# usbport-power-controller.net
KiCad netlist of a schematic drawn in EAGLE
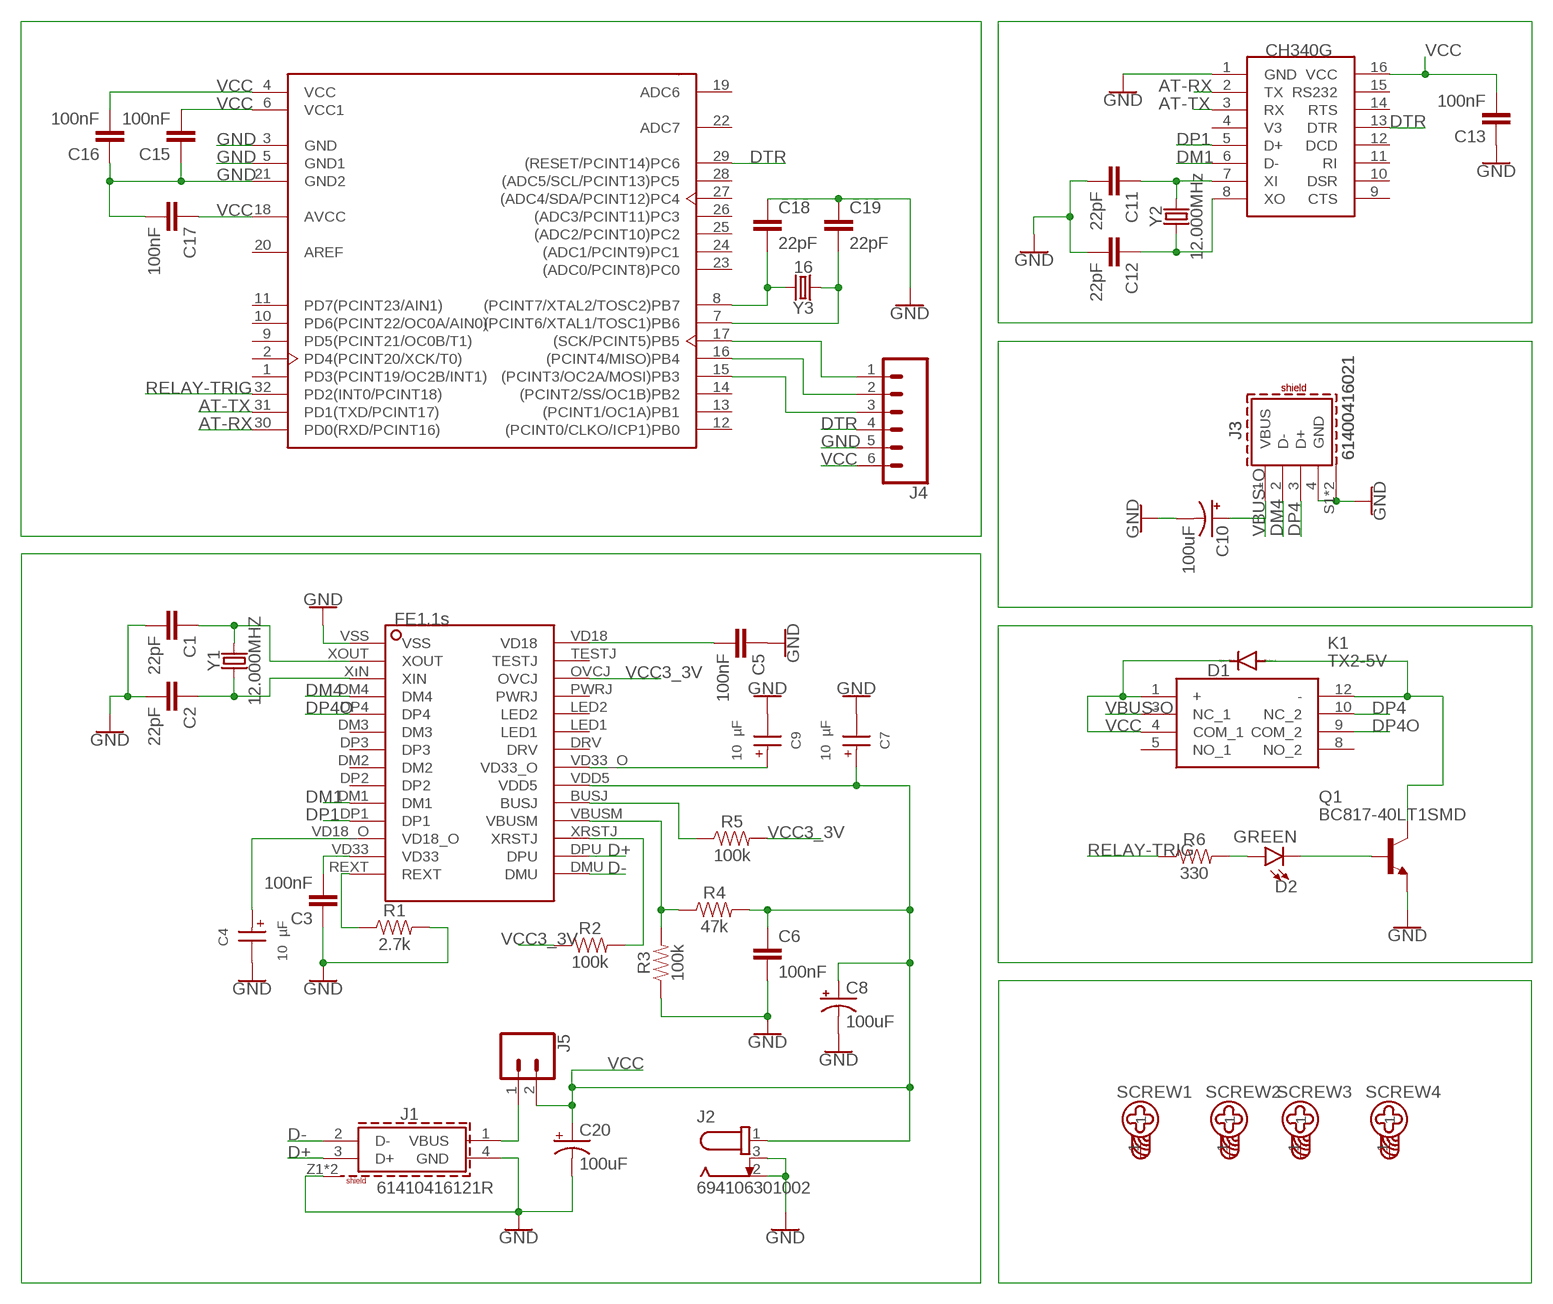
[diagram p0: schematic, sheet 1]

(export (version "E")
  (design (tool "Eeschema 10.0.6"))
  (components
    (comp (ref "ATMEGA328P-AU")
      (value "ATMEGA328P-AU")
      (footprint "eagle-import:TQFP-32")
      (fields
        (field (name "DIGIKEY_PART_NUMBER") "ATMEGA328P-AU-ND")
        (field (name "MANUFACTURER") "Microchip Technology")
        (field (name "CREATED_BY") "PCBLayout.com")
      )
      (libsource (lib "eagle-import") (part "ATMEGA328P-AU"))
    )
    (comp (ref "C1")
      (value "22pF")
      (footprint "eagle-import:1206")
      (libsource (lib "eagle-import") (part "10UF-1206-6.3V-20%"))
    )
    (comp (ref "C2")
      (value "22pF")
      (footprint "eagle-import:1206")
      (libsource (lib "eagle-import") (part "10UF-1206-6.3V-20%"))
    )
    (comp (ref "C3")
      (value "100nF")
      (footprint "eagle-import:1206")
      (libsource (lib "eagle-import") (part "1.0UF-1206-50V-10%"))
    )
    (comp (ref "C4")
      (value "10 µF")
      (footprint "eagle-import:WCAP-ASLI_4X5.5(DXL)")
      (libsource (lib "eagle-import") (part "WCAP-ASLI_4X5.5_865080340001"))
    )
    (comp (ref "C5")
      (value "100nF")
      (footprint "eagle-import:1206")
      (libsource (lib "eagle-import") (part "1.0UF-1206-50V-10%"))
    )
    (comp (ref "C6")
      (value "100nF")
      (footprint "eagle-import:1206")
      (libsource (lib "eagle-import") (part "1.0UF-1206-50V-10%"))
    )
    (comp (ref "C7")
      (value "10 µF")
      (footprint "eagle-import:WCAP-ASLI_4X5.5(DXL)")
      (libsource (lib "eagle-import") (part "WCAP-ASLI_4X5.5_865080340001"))
    )
    (comp (ref "C8")
      (value "100uF")
      (footprint "eagle-import:PANASONIC_D")
      (libsource (lib "eagle-import") (part "100UF-POLAR-25V-20%(ELEC)"))
    )
    (comp (ref "C9")
      (value "10 µF")
      (footprint "eagle-import:WCAP-ASLI_4X5.5(DXL)")
      (libsource (lib "eagle-import") (part "WCAP-ASLI_4X5.5_865080340001"))
    )
    (comp (ref "C10")
      (value "100uF")
      (footprint "eagle-import:PANASONIC_D")
      (libsource (lib "eagle-import") (part "100UF-POLAR-25V-20%(ELEC)"))
    )
    (comp (ref "C11")
      (value "22pF")
      (footprint "eagle-import:1206")
      (libsource (lib "eagle-import") (part "10UF-1206-6.3V-20%"))
    )
    (comp (ref "C12")
      (value "22pF")
      (footprint "eagle-import:1206")
      (libsource (lib "eagle-import") (part "10UF-1206-6.3V-20%"))
    )
    (comp (ref "C13")
      (value "100nF")
      (footprint "eagle-import:1206")
      (libsource (lib "eagle-import") (part "1.0UF-1206-50V-10%"))
    )
    (comp (ref "C15")
      (value "100nF")
      (footprint "eagle-import:1206")
      (libsource (lib "eagle-import") (part "1.0UF-1206-50V-10%"))
    )
    (comp (ref "C16")
      (value "100nF")
      (footprint "eagle-import:1206")
      (libsource (lib "eagle-import") (part "1.0UF-1206-50V-10%"))
    )
    (comp (ref "C17")
      (value "100nF")
      (footprint "eagle-import:1206")
      (libsource (lib "eagle-import") (part "1.0UF-1206-50V-10%"))
    )
    (comp (ref "C18")
      (value "22pF")
      (footprint "eagle-import:1206")
      (libsource (lib "eagle-import") (part "10UF-1206-6.3V-20%"))
    )
    (comp (ref "C19")
      (value "22pF")
      (footprint "eagle-import:1206")
      (libsource (lib "eagle-import") (part "10UF-1206-6.3V-20%"))
    )
    (comp (ref "C20")
      (value "100uF")
      (footprint "eagle-import:PANASONIC_D")
      (libsource (lib "eagle-import") (part "100UF-POLAR-25V-20%(ELEC)"))
    )
    (comp (ref "D1")
      (value "DIODE-DO-214AC")
      (footprint "eagle-import:DO-214AC")
      (libsource (lib "eagle-import") (part "DIODE-DO-214AC"))
    )
    (comp (ref "D2")
      (value "GREEN")
      (footprint "eagle-import:LED-1206")
      (libsource (lib "eagle-import") (part "LED-GREEN1206"))
    )
    (comp (ref "J1")
      (value "61410416121R")
      (footprint "eagle-import:61410416121R")
      (libsource (lib "eagle-import") (part "61410416121R"))
    )
    (comp (ref "J2")
      (value "694106301002")
      (footprint "eagle-import:694106301002")
      (fields
        (field (name "DIGIKEY_PART_NUMBER") "732-5930-ND")
        (field (name "MANUFACTURER") "Wurth Electronics Inc.")
        (field (name "CREATED_BY") "PCBLayout.com")
      )
      (libsource (lib "eagle-import") (part "694106301002"))
    )
    (comp (ref "J3")
      (value "61400416021")
      (footprint "eagle-import:61400416021")
      (libsource (lib "eagle-import") (part "61400416021"))
    )
    (comp (ref "J4")
      (value "CONN_06NO_SILK_FEMALE_PTH")
      (footprint "eagle-import:1X06_NO_SILK")
      (libsource (lib "eagle-import") (part "CONN_06NO_SILK_FEMALE_PTH"))
    )
    (comp (ref "J5")
      (value "CONN_02")
      (footprint "eagle-import:1X02")
      (libsource (lib "eagle-import") (part "CONN_02"))
    )
    (comp (ref "K1")
      (value "TX2-5V")
      (footprint "eagle-import:TX2-24V")
      (fields (field (name "MOUSER_PART_NUMBER") "769-TX2-5V"))
      (libsource (lib "eagle-import") (part "TX2-5V"))
    )
    (comp (ref "Q1")
      (value "BC817-40LT1SMD")
      (footprint "eagle-import:SOT23-BEC")
      (libsource (lib "eagle-import") (part "BC817SMD-40LT1"))
    )
    (comp (ref "R1")
      (value "2.7k")
      (footprint "eagle-import:1206")
      (libsource (lib "eagle-import") (part "RESISTOR1206"))
    )
    (comp (ref "R2")
      (value "100k")
      (footprint "eagle-import:1206")
      (libsource (lib "eagle-import") (part "RESISTOR1206"))
    )
    (comp (ref "R3")
      (value "100k")
      (footprint "eagle-import:1206")
      (libsource (lib "eagle-import") (part "RESISTOR1206"))
    )
    (comp (ref "R4")
      (value "47k")
      (footprint "eagle-import:1206")
      (libsource (lib "eagle-import") (part "RESISTOR1206"))
    )
    (comp (ref "R5")
      (value "100k")
      (footprint "eagle-import:1206")
      (libsource (lib "eagle-import") (part "RESISTOR1206"))
    )
    (comp (ref "R6")
      (value "330")
      (footprint "eagle-import:1206")
      (libsource (lib "eagle-import") (part "10OHM-1206-1/4W-1%"))
    )
    (comp (ref "SCREW1")
      (value "4946")
      (footprint "eagle-import:4946")
      (fields (field (name "MOUSER_PART_NUMBER") "534-4946"))
      (libsource (lib "eagle-import") (part "4946"))
    )
    (comp (ref "SCREW2")
      (value "4946")
      (footprint "eagle-import:4946")
      (fields (field (name "MOUSER_PART_NUMBER") "534-4946"))
      (libsource (lib "eagle-import") (part "4946"))
    )
    (comp (ref "SCREW3")
      (value "4946")
      (footprint "eagle-import:4946")
      (fields (field (name "MOUSER_PART_NUMBER") "534-4946"))
      (libsource (lib "eagle-import") (part "4946"))
    )
    (comp (ref "SCREW4")
      (value "4946")
      (footprint "eagle-import:4946")
      (fields (field (name "MOUSER_PART_NUMBER") "534-4946"))
      (libsource (lib "eagle-import") (part "4946"))
    )
    (comp (ref "U$1")
      (value "FE1.1S")
      (footprint "eagle-import:FE1.1S")
      (libsource (lib "eagle-import") (part "FE1.1S"))
    )
    (comp (ref "U$2")
      (value "CH340G")
      (footprint "eagle-import:SOIC16")
      (libsource (lib "eagle-import") (part "CH340G"))
    )
    (comp (ref "Y1")
      (value "12.000MHZ")
      (footprint "eagle-import:HC49UP")
      (libsource (lib "eagle-import") (part "CRYSTALSMD-HC49UP"))
    )
    (comp (ref "Y2")
      (value "12.000MHz")
      (footprint "eagle-import:HC49UP")
      (libsource (lib "eagle-import") (part "CRYSTALSMD-HC49UP"))
    )
    (comp (ref "Y3")
      (value "16")
      (footprint "eagle-import:HC49UP")
      (libsource (lib "eagle-import") (part "CRYSTALSMD-HC49UP"))
    )
  )
  (nets
    (net (code "1") (name "/AREF") (class "Default")
      (node (ref "ATMEGA328P-AU") (pin "20") (pinfunction "AREF_20") (pintype "power_in"))
    )
    (net (code "2") (name "/AT-RX") (class "Default")
      (node (ref "ATMEGA328P-AU") (pin "30") (pinfunction "PD0(RXD/PCINT16)_30") (pintype "bidirectional"))
      (node (ref "U$2") (pin "2") (pinfunction "TX_2") (pintype "bidirectional"))
    )
    (net (code "3") (name "/AT-TX") (class "Default")
      (node (ref "ATMEGA328P-AU") (pin "31") (pinfunction "PD1(TXD/PCINT17)_31") (pintype "bidirectional"))
      (node (ref "U$2") (pin "3") (pinfunction "RX_3") (pintype "bidirectional"))
    )
    (net (code "4") (name "/D+") (class "Default")
      (node (ref "J1") (pin "3") (pinfunction "D+_3") (pintype "bidirectional"))
      (node (ref "U$1") (pin "DPU") (pinfunction "DPU_DPU") (pintype "bidirectional"))
    )
    (net (code "5") (name "/D-") (class "Default")
      (node (ref "J1") (pin "2") (pinfunction "D-_2") (pintype "bidirectional"))
      (node (ref "U$1") (pin "DMU") (pinfunction "DMU_DMU") (pintype "bidirectional"))
    )
    (net (code "6") (name "/DM1") (class "Default")
      (node (ref "U$1") (pin "DM1") (pinfunction "DM1_DM1") (pintype "bidirectional"))
      (node (ref "U$2") (pin "6") (pinfunction "D-_6") (pintype "bidirectional"))
    )
    (net (code "7") (name "/DM4") (class "Default")
      (node (ref "J3") (pin "2") (pinfunction "D-_2") (pintype "bidirectional"))
      (node (ref "U$1") (pin "DM4") (pinfunction "DM4_DM4") (pintype "bidirectional"))
    )
    (net (code "8") (name "/DP1") (class "Default")
      (node (ref "U$1") (pin "DP1") (pinfunction "DP1_DP1") (pintype "bidirectional"))
      (node (ref "U$2") (pin "5") (pinfunction "D+_5") (pintype "bidirectional"))
    )
    (net (code "9") (name "/DP4") (class "Default")
      (node (ref "J3") (pin "3") (pinfunction "D+_3") (pintype "bidirectional"))
      (node (ref "K1") (pin "10") (pinfunction "NC_2_10") (pintype "bidirectional"))
    )
    (net (code "10") (name "/DP4O") (class "Default")
      (node (ref "K1") (pin "9") (pinfunction "COM_2_9") (pintype "bidirectional"))
      (node (ref "U$1") (pin "DP4") (pinfunction "DP4_DP4") (pintype "bidirectional"))
    )
    (net (code "11") (name "/DTR") (class "Default")
      (node (ref "ATMEGA328P-AU") (pin "29") (pinfunction "(RESET/PCINT14)PC6_29") (pintype "bidirectional"))
      (node (ref "J4") (pin "4") (pinfunction "4_4") (pintype "passive"))
      (node (ref "U$2") (pin "13") (pinfunction "DTR_13") (pintype "bidirectional"))
    )
    (net (code "12") (name "/RELAY-TRIG") (class "Default")
      (node (ref "ATMEGA328P-AU") (pin "32") (pinfunction "PD2(INT0/PCINT18)_32") (pintype "bidirectional"))
      (node (ref "R6") (pin "1") (pinfunction "1_1") (pintype "passive"))
    )
    (net (code "13") (name "/VBUS-O") (class "Default")
      (node (ref "C10") (pin "+") (pinfunction "+_+") (pintype "passive"))
      (node (ref "J3") (pin "1") (pinfunction "VBUS_1") (pintype "bidirectional"))
      (node (ref "K1") (pin "3") (pinfunction "NC_1_3") (pintype "bidirectional"))
    )
    (net (code "14") (name "/VCC") (class "Default")
      (node (ref "ATMEGA328P-AU") (pin "18") (pinfunction "AVCC_18") (pintype "power_in"))
      (node (ref "ATMEGA328P-AU") (pin "4") (pinfunction "VCC_4") (pintype "power_in"))
      (node (ref "ATMEGA328P-AU") (pin "6") (pinfunction "VCC1_6") (pintype "power_in"))
      (node (ref "C13") (pin "2") (pinfunction "2_2") (pintype "passive"))
      (node (ref "C15") (pin "2") (pinfunction "2_2") (pintype "passive"))
      (node (ref "C16") (pin "2") (pinfunction "2_2") (pintype "passive"))
      (node (ref "C17") (pin "1") (pinfunction "1_1") (pintype "passive"))
      (node (ref "C20") (pin "+") (pinfunction "+_+") (pintype "passive"))
      (node (ref "C6") (pin "1") (pinfunction "1_1") (pintype "passive"))
      (node (ref "C7") (pin "1") (pinfunction "+_1") (pintype "passive"))
      (node (ref "C8") (pin "+") (pinfunction "+_+") (pintype "passive"))
      (node (ref "D1") (pin "C") (pinfunction "C_C") (pintype "passive"))
      (node (ref "J2") (pin "1") (pinfunction "1_1") (pintype "passive"))
      (node (ref "J4") (pin "6") (pinfunction "6_6") (pintype "passive"))
      (node (ref "J5") (pin "2") (pinfunction "2_2") (pintype "passive"))
      (node (ref "K1") (pin "1") (pinfunction "+_1") (pintype "bidirectional"))
      (node (ref "K1") (pin "4") (pinfunction "COM_1_4") (pintype "bidirectional"))
      (node (ref "R4") (pin "2") (pinfunction "2_2") (pintype "passive"))
      (node (ref "U$1") (pin "VDD5") (pinfunction "VDD5_VDD5") (pintype "bidirectional"))
      (node (ref "U$2") (pin "16") (pinfunction "VCC_16") (pintype "bidirectional"))
    )
    (net (code "15") (name "/VCC3_3V") (class "Default")
      (node (ref "C9") (pin "1") (pinfunction "+_1") (pintype "passive"))
      (node (ref "R2") (pin "1") (pinfunction "1_1") (pintype "passive"))
      (node (ref "R5") (pin "2") (pinfunction "2_2") (pintype "passive"))
      (node (ref "U$1") (pin "OVCJ") (pinfunction "OVCJ_OVCJ") (pintype "bidirectional"))
      (node (ref "U$1") (pin "VD33_O") (pinfunction "VD33_O_VD33_O") (pintype "bidirectional"))
    )
    (net (code "16") (name "GND") (class "Default")
      (node (ref "ATMEGA328P-AU") (pin "21") (pinfunction "GND2_21") (pintype "power_in"))
      (node (ref "ATMEGA328P-AU") (pin "3") (pinfunction "GND_3") (pintype "power_in"))
      (node (ref "ATMEGA328P-AU") (pin "5") (pinfunction "GND1_5") (pintype "power_in"))
      (node (ref "C1") (pin "2") (pinfunction "2_2") (pintype "passive"))
      (node (ref "C10") (pin "-") (pinfunction "-_-") (pintype "passive"))
      (node (ref "C11") (pin "2") (pinfunction "2_2") (pintype "passive"))
      (node (ref "C12") (pin "2") (pinfunction "2_2") (pintype "passive"))
      (node (ref "C13") (pin "1") (pinfunction "1_1") (pintype "passive"))
      (node (ref "C15") (pin "1") (pinfunction "1_1") (pintype "passive"))
      (node (ref "C16") (pin "1") (pinfunction "1_1") (pintype "passive"))
      (node (ref "C17") (pin "2") (pinfunction "2_2") (pintype "passive"))
      (node (ref "C18") (pin "1") (pinfunction "1_1") (pintype "passive"))
      (node (ref "C19") (pin "1") (pinfunction "1_1") (pintype "passive"))
      (node (ref "C2") (pin "2") (pinfunction "2_2") (pintype "passive"))
      (node (ref "C20") (pin "-") (pinfunction "-_-") (pintype "passive"))
      (node (ref "C3") (pin "1") (pinfunction "1_1") (pintype "passive"))
      (node (ref "C4") (pin "2") (pinfunction "-_2") (pintype "passive"))
      (node (ref "C5") (pin "1") (pinfunction "1_1") (pintype "passive"))
      (node (ref "C6") (pin "2") (pinfunction "2_2") (pintype "passive"))
      (node (ref "C7") (pin "2") (pinfunction "-_2") (pintype "passive"))
      (node (ref "C8") (pin "-") (pinfunction "-_-") (pintype "passive"))
      (node (ref "C9") (pin "2") (pinfunction "-_2") (pintype "passive"))
      (node (ref "J1") (pin "4") (pinfunction "GND_4") (pintype "bidirectional"))
      (node (ref "J1") (pin "Z1") (pinfunction "SHIELD_Z1") (pintype "bidirectional"))
      (node (ref "J1") (pin "Z2") (pinfunction "SHIELD_Z2") (pintype "bidirectional"))
      (node (ref "J2") (pin "2") (pinfunction "2_2") (pintype "passive"))
      (node (ref "J2") (pin "3") (pinfunction "3_3") (pintype "passive"))
      (node (ref "J3") (pin "4") (pinfunction "GND_4") (pintype "bidirectional"))
      (node (ref "J3") (pin "S1") (pinfunction "SHIELD_S1") (pintype "bidirectional"))
      (node (ref "J3") (pin "S2") (pinfunction "SHIELD_S2") (pintype "bidirectional"))
      (node (ref "J4") (pin "5") (pinfunction "5_5") (pintype "passive"))
      (node (ref "Q1") (pin "E") (pinfunction "E_E") (pintype "passive"))
      (node (ref "R1") (pin "2") (pinfunction "2_2") (pintype "passive"))
      (node (ref "R3") (pin "1") (pinfunction "1_1") (pintype "passive"))
      (node (ref "U$1") (pin "VSS") (pinfunction "VSS_VSS") (pintype "bidirectional"))
      (node (ref "U$2") (pin "1") (pinfunction "GND_1") (pintype "bidirectional"))
    )
    (net (code "17") (name "Net-(ATMEGA328P-AU-(PCINT3{slash}OC2A{slash}MOSI)PB3)") (class "Default")
      (node (ref "ATMEGA328P-AU") (pin "15") (pinfunction "(PCINT3/OC2A/MOSI)PB3_15") (pintype "bidirectional"))
      (node (ref "J4") (pin "3") (pinfunction "3_3") (pintype "passive"))
    )
    (net (code "18") (name "Net-(ATMEGA328P-AU-(PCINT4{slash}MISO)PB4)") (class "Default")
      (node (ref "ATMEGA328P-AU") (pin "16") (pinfunction "(PCINT4/MISO)PB4_16") (pintype "bidirectional"))
      (node (ref "J4") (pin "2") (pinfunction "2_2") (pintype "passive"))
    )
    (net (code "19") (name "Net-(ATMEGA328P-AU-(PCINT6{slash}XTAL1{slash}TOSC1)PB6)") (class "Default")
      (node (ref "ATMEGA328P-AU") (pin "7") (pinfunction "(PCINT6/XTAL1/TOSC1)PB6_7") (pintype "bidirectional"))
      (node (ref "C19") (pin "2") (pinfunction "2_2") (pintype "passive"))
      (node (ref "Y3") (pin "1") (pinfunction "1_1") (pintype "passive"))
    )
    (net (code "20") (name "Net-(ATMEGA328P-AU-(PCINT7{slash}XTAL2{slash}TOSC2)PB7)") (class "Default")
      (node (ref "ATMEGA328P-AU") (pin "8") (pinfunction "(PCINT7/XTAL2/TOSC2)PB7_8") (pintype "bidirectional"))
      (node (ref "C18") (pin "2") (pinfunction "2_2") (pintype "passive"))
      (node (ref "Y3") (pin "2") (pinfunction "2_2") (pintype "passive"))
    )
    (net (code "21") (name "Net-(ATMEGA328P-AU-(SCK{slash}PCINT5)PB5)") (class "Default")
      (node (ref "ATMEGA328P-AU") (pin "17") (pinfunction "(SCK/PCINT5)PB5_17") (pintype "bidirectional"))
      (node (ref "J4") (pin "1") (pinfunction "1_1") (pintype "passive"))
    )
    (net (code "22") (name "Net-(C1-Pad1)") (class "Default")
      (node (ref "C1") (pin "1") (pinfunction "1_1") (pintype "passive"))
      (node (ref "U$1") (pin "XOUT") (pinfunction "XOUT_XOUT") (pintype "bidirectional"))
      (node (ref "Y1") (pin "2") (pinfunction "2_2") (pintype "passive"))
    )
    (net (code "23") (name "Net-(C3-Pad2)") (class "Default")
      (node (ref "C3") (pin "2") (pinfunction "2_2") (pintype "passive"))
      (node (ref "U$1") (pin "VD33") (pinfunction "VD33_VD33") (pintype "bidirectional"))
    )
    (net (code "24") (name "Net-(C4-+)") (class "Default")
      (node (ref "C4") (pin "1") (pinfunction "+_1") (pintype "passive"))
      (node (ref "U$1") (pin "VD18_O") (pinfunction "VD18_O_VD18_O") (pintype "bidirectional"))
    )
    (net (code "25") (name "Net-(C5-Pad2)") (class "Default")
      (node (ref "C5") (pin "2") (pinfunction "2_2") (pintype "passive"))
      (node (ref "U$1") (pin "VD18") (pinfunction "VD18_VD18") (pintype "bidirectional"))
    )
    (net (code "26") (name "Net-(D2-PadA)") (class "Default")
      (node (ref "D2") (pin "A") (pinfunction "A_A") (pintype "passive"))
      (node (ref "R6") (pin "2") (pinfunction "2_2") (pintype "passive"))
    )
    (net (code "27") (name "Net-(D2-PadC)") (class "Default")
      (node (ref "D2") (pin "C") (pinfunction "C_C") (pintype "passive"))
      (node (ref "Q1") (pin "B") (pinfunction "B_B") (pintype "passive"))
    )
    (net (code "28") (name "Net-(J1-VBUS)") (class "Default")
      (node (ref "J1") (pin "1") (pinfunction "VBUS_1") (pintype "bidirectional"))
      (node (ref "J5") (pin "1") (pinfunction "1_1") (pintype "passive"))
    )
    (net (code "29") (name "Net-(K1--)") (class "Default")
      (node (ref "D1") (pin "A") (pinfunction "A_A") (pintype "passive"))
      (node (ref "K1") (pin "12") (pinfunction "-_12") (pintype "bidirectional"))
      (node (ref "Q1") (pin "C") (pinfunction "C_C") (pintype "passive"))
    )
    (net (code "30") (name "Net-(R1-Pad1)") (class "Default")
      (node (ref "R1") (pin "1") (pinfunction "1_1") (pintype "passive"))
      (node (ref "U$1") (pin "REXT") (pinfunction "REXT_REXT") (pintype "bidirectional"))
    )
    (net (code "31") (name "Net-(R2-Pad2)") (class "Default")
      (node (ref "R2") (pin "2") (pinfunction "2_2") (pintype "passive"))
      (node (ref "U$1") (pin "XRSTJ") (pinfunction "XRSTJ_XRSTJ") (pintype "bidirectional"))
    )
    (net (code "32") (name "Net-(R3-Pad2)") (class "Default")
      (node (ref "R3") (pin "2") (pinfunction "2_2") (pintype "passive"))
      (node (ref "R4") (pin "1") (pinfunction "1_1") (pintype "passive"))
      (node (ref "U$1") (pin "VBUSM") (pinfunction "VBUSM_VBUSM") (pintype "bidirectional"))
    )
    (net (code "33") (name "Net-(R5-Pad1)") (class "Default")
      (node (ref "R5") (pin "1") (pinfunction "1_1") (pintype "passive"))
      (node (ref "U$1") (pin "BUSJ") (pinfunction "BUSJ_BUSJ") (pintype "bidirectional"))
    )
    (net (code "34") (name "Net-(U$1-XIN)") (class "Default")
      (node (ref "C2") (pin "1") (pinfunction "1_1") (pintype "passive"))
      (node (ref "U$1") (pin "XıN") (pinfunction "XIN_XıN") (pintype "bidirectional"))
      (node (ref "Y1") (pin "1") (pinfunction "1_1") (pintype "passive"))
    )
    (net (code "35") (name "Net-(U$2-XI)") (class "Default")
      (node (ref "C11") (pin "1") (pinfunction "1_1") (pintype "passive"))
      (node (ref "U$2") (pin "7") (pinfunction "XI_7") (pintype "bidirectional"))
      (node (ref "Y2") (pin "2") (pinfunction "2_2") (pintype "passive"))
    )
    (net (code "36") (name "Net-(U$2-XO)") (class "Default")
      (node (ref "C12") (pin "1") (pinfunction "1_1") (pintype "passive"))
      (node (ref "U$2") (pin "8") (pinfunction "XO_8") (pintype "bidirectional"))
      (node (ref "Y2") (pin "1") (pinfunction "1_1") (pintype "passive"))
    )
    (net (code "37") (name "unconnected-(ATMEGA328P-AU-(ADC0{slash}PCINT8)PC0-Pad23)") (class "Default")
      (node (ref "ATMEGA328P-AU") (pin "23") (pinfunction "(ADC0/PCINT8)PC0_23") (pintype "bidirectional"))
    )
    (net (code "38") (name "unconnected-(ATMEGA328P-AU-(ADC1{slash}PCINT9)PC1-Pad24)") (class "Default")
      (node (ref "ATMEGA328P-AU") (pin "24") (pinfunction "(ADC1/PCINT9)PC1_24") (pintype "bidirectional"))
    )
    (net (code "39") (name "unconnected-(ATMEGA328P-AU-(ADC2{slash}PCINT10)PC2-Pad25)") (class "Default")
      (node (ref "ATMEGA328P-AU") (pin "25") (pinfunction "(ADC2/PCINT10)PC2_25") (pintype "bidirectional"))
    )
    (net (code "40") (name "unconnected-(ATMEGA328P-AU-(ADC3{slash}PCINT11)PC3-Pad26)") (class "Default")
      (node (ref "ATMEGA328P-AU") (pin "26") (pinfunction "(ADC3/PCINT11)PC3_26") (pintype "bidirectional"))
    )
    (net (code "41") (name "unconnected-(ATMEGA328P-AU-(ADC4{slash}SDA{slash}PCINT12)PC4-Pad27)") (class "Default")
      (node (ref "ATMEGA328P-AU") (pin "27") (pinfunction "(ADC4/SDA/PCINT12)PC4_27") (pintype "bidirectional"))
    )
    (net (code "42") (name "unconnected-(ATMEGA328P-AU-(ADC5{slash}SCL{slash}PCINT13)PC5-Pad28)") (class "Default")
      (node (ref "ATMEGA328P-AU") (pin "28") (pinfunction "(ADC5/SCL/PCINT13)PC5_28") (pintype "bidirectional"))
    )
    (net (code "43") (name "unconnected-(ATMEGA328P-AU-(PCINT0{slash}CLKO{slash}ICP1)PB0-Pad12)") (class "Default")
      (node (ref "ATMEGA328P-AU") (pin "12") (pinfunction "(PCINT0/CLKO/ICP1)PB0_12") (pintype "bidirectional"))
    )
    (net (code "44") (name "unconnected-(ATMEGA328P-AU-(PCINT1{slash}OC1A)PB1-Pad13)") (class "Default")
      (node (ref "ATMEGA328P-AU") (pin "13") (pinfunction "(PCINT1/OC1A)PB1_13") (pintype "bidirectional"))
    )
    (net (code "45") (name "unconnected-(ATMEGA328P-AU-(PCINT2{slash}SS{slash}OC1B)PB2-Pad14)") (class "Default")
      (node (ref "ATMEGA328P-AU") (pin "14") (pinfunction "(PCINT2/SS/OC1B)PB2_14") (pintype "bidirectional"))
    )
    (net (code "46") (name "unconnected-(ATMEGA328P-AU-ADC6-Pad19)") (class "Default")
      (node (ref "ATMEGA328P-AU") (pin "19") (pinfunction "ADC6_19") (pintype "input"))
    )
    (net (code "47") (name "unconnected-(ATMEGA328P-AU-ADC7-Pad22)") (class "Default")
      (node (ref "ATMEGA328P-AU") (pin "22") (pinfunction "ADC7_22") (pintype "input"))
    )
    (net (code "48") (name "unconnected-(ATMEGA328P-AU-PD3(PCINT19{slash}OC2B{slash}INT1)-Pad1)") (class "Default")
      (node (ref "ATMEGA328P-AU") (pin "1") (pinfunction "PD3(PCINT19/OC2B/INT1)_1") (pintype "bidirectional"))
    )
    (net (code "49") (name "unconnected-(ATMEGA328P-AU-PD4(PCINT20{slash}XCK{slash}T0)-Pad2)") (class "Default")
      (node (ref "ATMEGA328P-AU") (pin "2") (pinfunction "PD4(PCINT20/XCK/T0)_2") (pintype "bidirectional"))
    )
    (net (code "50") (name "unconnected-(ATMEGA328P-AU-PD5(PCINT21{slash}OC0B{slash}T1)-Pad9)") (class "Default")
      (node (ref "ATMEGA328P-AU") (pin "9") (pinfunction "PD5(PCINT21/OC0B/T1)_9") (pintype "bidirectional"))
    )
    (net (code "51") (name "unconnected-(ATMEGA328P-AU-PD6(PCINT22{slash}OC0A{slash}AIN0)-Pad10)") (class "Default")
      (node (ref "ATMEGA328P-AU") (pin "10") (pinfunction "PD6(PCINT22/OC0A/AIN0)_10") (pintype "bidirectional"))
    )
    (net (code "52") (name "unconnected-(ATMEGA328P-AU-PD7(PCINT23{slash}AIN1)-Pad11)") (class "Default")
      (node (ref "ATMEGA328P-AU") (pin "11") (pinfunction "PD7(PCINT23/AIN1)_11") (pintype "bidirectional"))
    )
    (net (code "53") (name "unconnected-(K1-NO_1-Pad5)") (class "Default")
      (node (ref "K1") (pin "5") (pinfunction "NO_1_5") (pintype "bidirectional"))
    )
    (net (code "54") (name "unconnected-(K1-NO_2-Pad8)") (class "Default")
      (node (ref "K1") (pin "8") (pinfunction "NO_2_8") (pintype "bidirectional"))
    )
    (net (code "55") (name "unconnected-(SCREW1-Pad1)") (class "Default")
      (node (ref "SCREW1") (pin "1") (pinfunction "1_1") (pintype "bidirectional"))
    )
    (net (code "56") (name "unconnected-(SCREW2-Pad1)") (class "Default")
      (node (ref "SCREW2") (pin "1") (pinfunction "1_1") (pintype "bidirectional"))
    )
    (net (code "57") (name "unconnected-(SCREW3-Pad1)") (class "Default")
      (node (ref "SCREW3") (pin "1") (pinfunction "1_1") (pintype "bidirectional"))
    )
    (net (code "58") (name "unconnected-(SCREW4-Pad1)") (class "Default")
      (node (ref "SCREW4") (pin "1") (pinfunction "1_1") (pintype "bidirectional"))
    )
    (net (code "59") (name "unconnected-(U$1-PadDM2)") (class "Default")
      (node (ref "U$1") (pin "DM2") (pinfunction "DM2_DM2") (pintype "bidirectional"))
    )
    (net (code "60") (name "unconnected-(U$1-PadDM3)") (class "Default")
      (node (ref "U$1") (pin "DM3") (pinfunction "DM3_DM3") (pintype "bidirectional"))
    )
    (net (code "61") (name "unconnected-(U$1-PadDP2)") (class "Default")
      (node (ref "U$1") (pin "DP2") (pinfunction "DP2_DP2") (pintype "bidirectional"))
    )
    (net (code "62") (name "unconnected-(U$1-PadDP3)") (class "Default")
      (node (ref "U$1") (pin "DP3") (pinfunction "DP3_DP3") (pintype "bidirectional"))
    )
    (net (code "63") (name "unconnected-(U$1-PadDRV)") (class "Default")
      (node (ref "U$1") (pin "DRV") (pinfunction "DRV_DRV") (pintype "bidirectional"))
    )
    (net (code "64") (name "unconnected-(U$1-PadLED1)") (class "Default")
      (node (ref "U$1") (pin "LED1") (pinfunction "LED1_LED1") (pintype "bidirectional"))
    )
    (net (code "65") (name "unconnected-(U$1-PadLED2)") (class "Default")
      (node (ref "U$1") (pin "LED2") (pinfunction "LED2_LED2") (pintype "bidirectional"))
    )
    (net (code "66") (name "unconnected-(U$1-PadPWRJ)") (class "Default")
      (node (ref "U$1") (pin "PWRJ") (pinfunction "PWRJ_PWRJ") (pintype "bidirectional"))
    )
    (net (code "67") (name "unconnected-(U$1-PadTESTJ)") (class "Default")
      (node (ref "U$1") (pin "TESTJ") (pinfunction "TESTJ_TESTJ") (pintype "bidirectional"))
    )
    (net (code "68") (name "unconnected-(U$2-CTS-Pad9)") (class "Default")
      (node (ref "U$2") (pin "9") (pinfunction "CTS_9") (pintype "bidirectional"))
    )
    (net (code "69") (name "unconnected-(U$2-DCD-Pad12)") (class "Default")
      (node (ref "U$2") (pin "12") (pinfunction "DCD_12") (pintype "bidirectional"))
    )
    (net (code "70") (name "unconnected-(U$2-DSR-Pad10)") (class "Default")
      (node (ref "U$2") (pin "10") (pinfunction "DSR_10") (pintype "bidirectional"))
    )
    (net (code "71") (name "unconnected-(U$2-RI-Pad11)") (class "Default")
      (node (ref "U$2") (pin "11") (pinfunction "RI_11") (pintype "bidirectional"))
    )
    (net (code "72") (name "unconnected-(U$2-RS232-Pad15)") (class "Default")
      (node (ref "U$2") (pin "15") (pinfunction "RS232_15") (pintype "bidirectional"))
    )
    (net (code "73") (name "unconnected-(U$2-RTS-Pad14)") (class "Default")
      (node (ref "U$2") (pin "14") (pinfunction "RTS_14") (pintype "bidirectional"))
    )
    (net (code "74") (name "unconnected-(U$2-V3-Pad4)") (class "Default")
      (node (ref "U$2") (pin "4") (pinfunction "V3_4") (pintype "bidirectional"))
    )
  )
)
